# diban_v0_0.net
KiCad netlist of a schematic drawn in Altium Designer
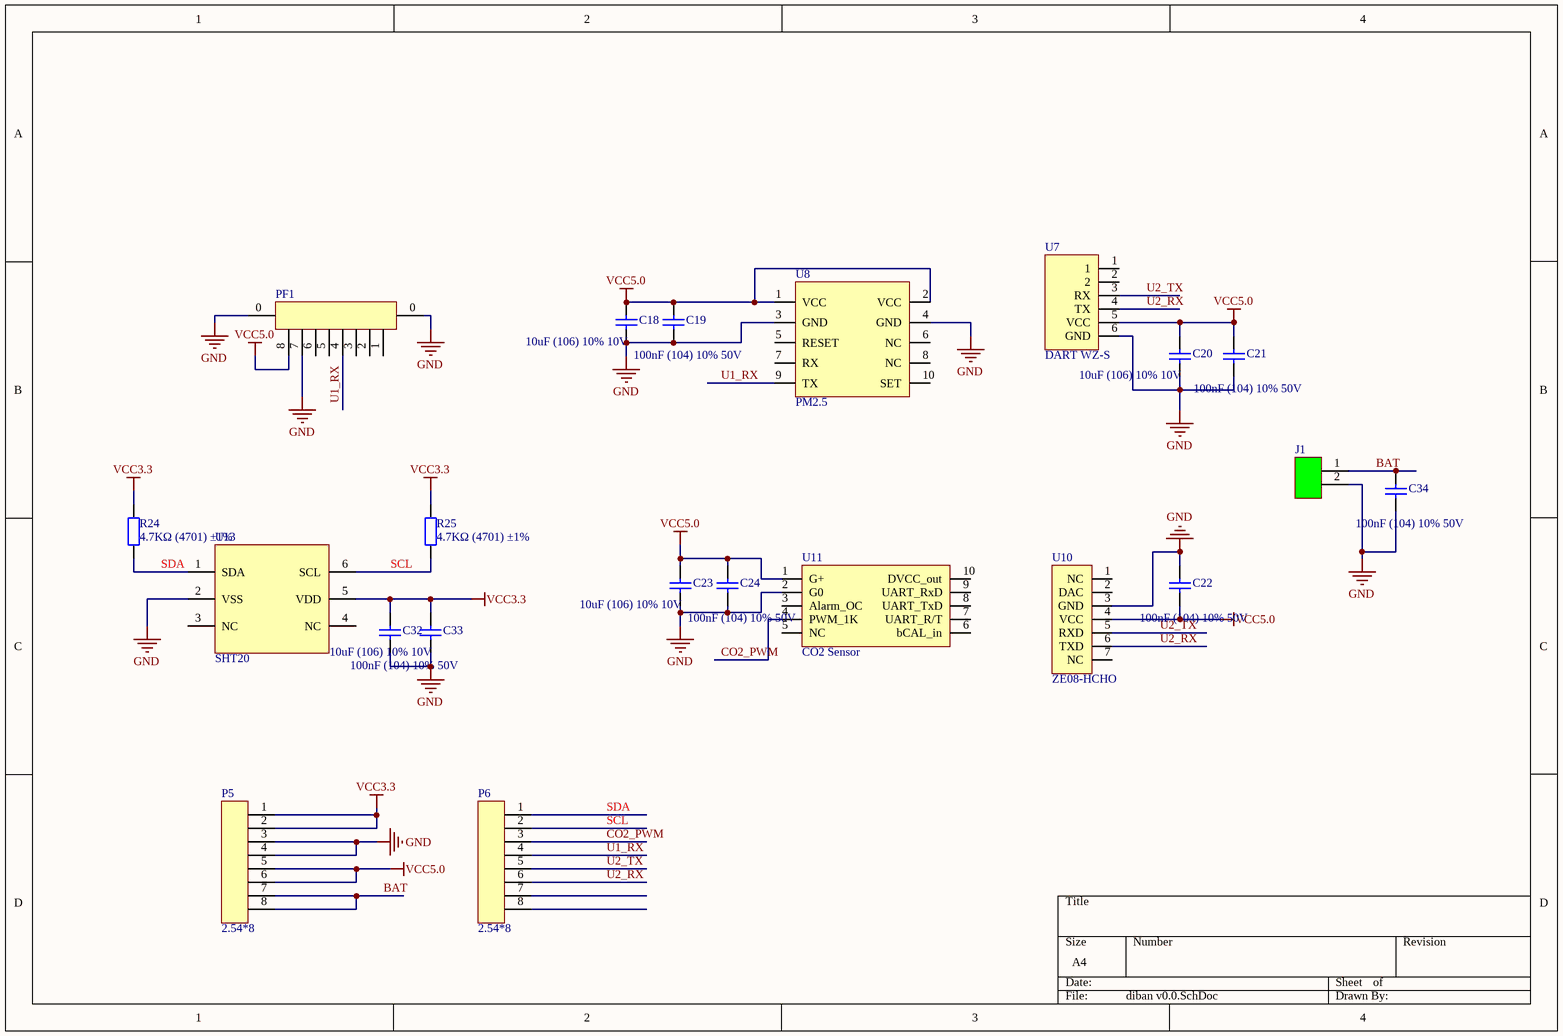
[diagram p0: diban v0.0.SchDoc]

(export (version "E")
  (design (tool "Eeschema 10.0.6"))
  (components
    (comp (ref "C18")
      (value "10uF (106) 10% 10V")
      (footprint "0603_C")
      (description "贴片电容")
      (libsource (lib "Miscellaneous Devices LC") (part "0603 10uF (106) 10% 10V"))
    )
    (comp (ref "C19")
      (value "100nF (104) 10% 50V")
      (footprint "0603_C")
      (description "贴片电容")
      (libsource (lib "Miscellaneous Devices LC") (part "0603 100nF (104) 10% 50V"))
    )
    (comp (ref "C20")
      (value "10uF (106) 10% 10V")
      (footprint "0603_C")
      (description "贴片电容")
      (libsource (lib "Miscellaneous Devices LC") (part "0603 10uF (106) 10% 10V"))
    )
    (comp (ref "C21")
      (value "100nF (104) 10% 50V")
      (footprint "0603_C")
      (description "贴片电容")
      (libsource (lib "Miscellaneous Devices LC") (part "0603 100nF (104) 10% 50V"))
    )
    (comp (ref "C22")
      (value "100nF (104) 10% 50V")
      (footprint "0603_C")
      (description "贴片电容")
      (libsource (lib "Miscellaneous Devices LC") (part "0603 100nF (104) 10% 50V"))
    )
    (comp (ref "C23")
      (value "10uF (106) 10% 10V")
      (footprint "0603_C")
      (description "贴片电容")
      (libsource (lib "Miscellaneous Devices LC") (part "0603 10uF (106) 10% 10V"))
    )
    (comp (ref "C24")
      (value "100nF (104) 10% 50V")
      (footprint "0603_C")
      (description "贴片电容")
      (libsource (lib "Miscellaneous Devices LC") (part "0603 100nF (104) 10% 50V"))
    )
    (comp (ref "C32")
      (value "100nF (104) 10% 50V")
      (footprint "0603_C")
      (description "贴片电容")
      (libsource (lib "Miscellaneous Devices LC") (part "0603 100nF (104) 10% 50V"))
    )
    (comp (ref "C33")
      (value "10uF (106) 10% 10V")
      (footprint "0603_C")
      (description "贴片电容")
      (libsource (lib "Miscellaneous Devices LC") (part "0603 10uF (106) 10% 10V"))
    )
    (comp (ref "C34")
      (value "100nF (104) 10% 50V")
      (footprint "0603_C")
      (description "贴片电容")
      (libsource (lib "Miscellaneous Devices LC") (part "0603 100nF (104) 10% 50V"))
    )
    (comp (ref "J1") (value "3.5mm-2p") (footprint "3.5mm-2p") (libsource (lib "接插件") (part "3.5mm-2p")))
    (comp (ref "P5") (value "2.54*8") (footprint "2.54*8") (libsource (lib "接插件") (part "2.54*8")))
    (comp (ref "P6") (value "2.54*8") (footprint "2.54*8") (libsource (lib "接插件") (part "2.54*8")))
    (comp (ref "PF1") (value "PCF-8") (footprint "PCF-8") (libsource (lib "接插件") (part "PCF-8")))
    (comp (ref "R24")
      (value "4.7KΩ (4701) ±1%")
      (footprint "0603_R")
      (description "贴片电阻")
      (libsource (lib "Miscellaneous Devices LC") (part "0603 4.7KΩ (4701) 1%"))
    )
    (comp (ref "R25")
      (value "4.7KΩ (4701) ±1%")
      (footprint "0603_R")
      (description "贴片电阻")
      (libsource (lib "Miscellaneous Devices LC") (part "0603 4.7KΩ (4701) 1%"))
    )
    (comp (ref "U7") (value "DART WZ-S") (footprint "DART WZ-S") (libsource (lib "集成块") (part "DART WZ-S")))
    (comp (ref "U8") (value "PM2.5") (footprint "PM2.5") (libsource (lib "集成块") (part "PM2.5")))
    (comp (ref "U10") (value "ZE08-HCHO") (footprint "ZE08-HCHO") (libsource (lib "集成块") (part "ZE08-HCHO")))
    (comp (ref "U11")
      (value "CO2 Sensor")
      (footprint "CO2 Sensor")
      (libsource (lib "集成块") (part "CO2 Sensor"))
    )
    (comp (ref "U13") (value "SHT20") (footprint "SHT20") (libsource (lib "集成块") (part "SHT20")))
  )
  (nets
    (net (code "1") (name "/BAT") (class "Default")
      (node (ref "C34") (pin "2") (pinfunction "2_2") (pintype "passive"))
      (node (ref "J1") (pin "1") (pintype "passive"))
      (node (ref "P5") (pin "7") (pintype "passive"))
      (node (ref "P5") (pin "8") (pinfunction "8_8") (pintype "passive"))
    )
    (net (code "2") (name "/CO2_PWM") (class "Default")
      (node (ref "P6") (pin "3") (pintype "passive"))
      (node (ref "U11") (pin "4") (pinfunction "PWM_1K_4") (pintype "passive"))
    )
    (net (code "3") (name "/SCL") (class "Default")
      (node (ref "P6") (pin "2") (pintype "passive"))
      (node (ref "R25") (pin "1") (pinfunction "1_1") (pintype "passive"))
      (node (ref "U13") (pin "6") (pinfunction "SCL_6") (pintype "passive"))
    )
    (net (code "4") (name "/SDA") (class "Default")
      (node (ref "P6") (pin "1") (pintype "passive"))
      (node (ref "R24") (pin "1") (pinfunction "1_1") (pintype "passive"))
      (node (ref "U13") (pin "1") (pinfunction "SDA_1") (pintype "passive"))
    )
    (net (code "5") (name "/U1_RX") (class "Default")
      (node (ref "P6") (pin "4") (pintype "passive"))
      (node (ref "PF1") (pin "4") (pintype "passive"))
      (node (ref "U8") (pin "9") (pinfunction "TX_9") (pintype "passive"))
    )
    (net (code "6") (name "/U2_RX") (class "Default")
      (node (ref "P6") (pin "6") (pintype "passive"))
      (node (ref "U10") (pin "6") (pinfunction "TXD_6") (pintype "passive"))
      (node (ref "U7") (pin "4") (pinfunction "TX_4") (pintype "passive"))
    )
    (net (code "7") (name "/U2_TX") (class "Default")
      (node (ref "P6") (pin "5") (pintype "passive"))
      (node (ref "U10") (pin "5") (pinfunction "RXD_5") (pintype "passive"))
      (node (ref "U7") (pin "3") (pinfunction "RX_3") (pintype "passive"))
    )
    (net (code "8") (name "GND") (class "Default")
      (node (ref "C18") (pin "1") (pinfunction "1_1") (pintype "passive"))
      (node (ref "C19") (pin "1") (pinfunction "1_1") (pintype "passive"))
      (node (ref "C20") (pin "1") (pinfunction "1_1") (pintype "passive"))
      (node (ref "C21") (pin "1") (pinfunction "1_1") (pintype "passive"))
      (node (ref "C22") (pin "2") (pinfunction "2_2") (pintype "passive"))
      (node (ref "C23") (pin "1") (pinfunction "1_1") (pintype "passive"))
      (node (ref "C24") (pin "1") (pinfunction "1_1") (pintype "passive"))
      (node (ref "C32") (pin "1") (pinfunction "1_1") (pintype "passive"))
      (node (ref "C33") (pin "1") (pinfunction "1_1") (pintype "passive"))
      (node (ref "C34") (pin "1") (pinfunction "1_1") (pintype "passive"))
      (node (ref "J1") (pin "2") (pintype "passive"))
      (node (ref "P5") (pin "3") (pintype "passive"))
      (node (ref "P5") (pin "4") (pintype "passive"))
      (node (ref "PF1") (pin "0") (pintype "passive"))
      (node (ref "PF1") (pin "7") (pintype "passive"))
      (node (ref "U10") (pin "3") (pinfunction "GND_3") (pintype "passive"))
      (node (ref "U11") (pin "2") (pinfunction "G0_2") (pintype "passive"))
      (node (ref "U13") (pin "2") (pinfunction "VSS_2") (pintype "passive"))
      (node (ref "U7") (pin "6") (pinfunction "GND_6") (pintype "passive"))
      (node (ref "U8") (pin "3") (pinfunction "GND_3") (pintype "passive"))
      (node (ref "U8") (pin "4") (pinfunction "GND_4") (pintype "passive"))
    )
    (net (code "9") (name "VCC3.3") (class "Default")
      (node (ref "C32") (pin "2") (pinfunction "2_2") (pintype "passive"))
      (node (ref "C33") (pin "2") (pinfunction "2_2") (pintype "passive"))
      (node (ref "P5") (pin "1") (pintype "passive"))
      (node (ref "P5") (pin "2") (pintype "passive"))
      (node (ref "R24") (pin "2") (pinfunction "2_2") (pintype "passive"))
      (node (ref "R25") (pin "2") (pinfunction "2_2") (pintype "passive"))
      (node (ref "U13") (pin "5") (pinfunction "VDD_5") (pintype "passive"))
    )
    (net (code "10") (name "VCC5.0") (class "Default")
      (node (ref "C18") (pin "2") (pinfunction "2_2") (pintype "passive"))
      (node (ref "C19") (pin "2") (pinfunction "2_2") (pintype "passive"))
      (node (ref "C20") (pin "2") (pinfunction "2_2") (pintype "passive"))
      (node (ref "C21") (pin "2") (pinfunction "2_2") (pintype "passive"))
      (node (ref "C22") (pin "1") (pinfunction "1_1") (pintype "passive"))
      (node (ref "C23") (pin "2") (pinfunction "2_2") (pintype "passive"))
      (node (ref "C24") (pin "2") (pinfunction "2_2") (pintype "passive"))
      (node (ref "P5") (pin "5") (pintype "passive"))
      (node (ref "P5") (pin "6") (pintype "passive"))
      (node (ref "PF1") (pin "8") (pinfunction "8_8") (pintype "passive"))
      (node (ref "U10") (pin "4") (pinfunction "VCC_4") (pintype "passive"))
      (node (ref "U11") (pin "1") (pinfunction "G+_1") (pintype "passive"))
      (node (ref "U7") (pin "5") (pinfunction "VCC_5") (pintype "passive"))
      (node (ref "U8") (pin "1") (pinfunction "VCC_1") (pintype "passive"))
      (node (ref "U8") (pin "2") (pinfunction "VCC_2") (pintype "passive"))
    )
    (net (code "11") (name "unconnected-(P6-Pad7)") (class "Default")
      (node (ref "P6") (pin "7") (pintype "passive"))
    )
    (net (code "12") (name "unconnected-(P6-Pad8)") (class "Default")
      (node (ref "P6") (pin "8") (pinfunction "8_8") (pintype "passive"))
    )
    (net (code "13") (name "unconnected-(PF1-Pad1)") (class "Default")
      (node (ref "PF1") (pin "1") (pintype "passive"))
    )
    (net (code "14") (name "unconnected-(PF1-Pad2)") (class "Default")
      (node (ref "PF1") (pin "2") (pintype "passive"))
    )
    (net (code "15") (name "unconnected-(PF1-Pad3)") (class "Default")
      (node (ref "PF1") (pin "3") (pintype "passive"))
    )
    (net (code "16") (name "unconnected-(PF1-Pad5)") (class "Default")
      (node (ref "PF1") (pin "5") (pintype "passive"))
    )
    (net (code "17") (name "unconnected-(PF1-Pad6)") (class "Default")
      (node (ref "PF1") (pin "6") (pintype "passive"))
    )
    (net (code "18") (name "unconnected-(U7-Pad1)") (class "Default")
      (node (ref "U7") (pin "1") (pinfunction "1_1") (pintype "passive"))
    )
    (net (code "19") (name "unconnected-(U7-Pad2)") (class "Default")
      (node (ref "U7") (pin "2") (pinfunction "2_2") (pintype "passive"))
    )
    (net (code "20") (name "unconnected-(U8-NC-Pad6)") (class "Default")
      (node (ref "U8") (pin "6") (pinfunction "NC_6") (pintype "passive"))
    )
    (net (code "21") (name "unconnected-(U8-NC-Pad8)") (class "Default")
      (node (ref "U8") (pin "8") (pinfunction "NC_8") (pintype "passive"))
    )
    (net (code "22") (name "unconnected-(U8-RESET-Pad5)") (class "Default")
      (node (ref "U8") (pin "5") (pinfunction "RESET_5") (pintype "passive"))
    )
    (net (code "23") (name "unconnected-(U8-RX-Pad7)") (class "Default")
      (node (ref "U8") (pin "7") (pinfunction "RX_7") (pintype "passive"))
    )
    (net (code "24") (name "unconnected-(U8-SET-Pad10)") (class "Default")
      (node (ref "U8") (pin "10") (pinfunction "SET_10") (pintype "passive"))
    )
    (net (code "25") (name "unconnected-(U10-DAC-Pad2)") (class "Default")
      (node (ref "U10") (pin "2") (pinfunction "DAC_2") (pintype "passive"))
    )
    (net (code "26") (name "unconnected-(U10-NC-Pad1)") (class "Default")
      (node (ref "U10") (pin "1") (pinfunction "NC_1") (pintype "passive"))
    )
    (net (code "27") (name "unconnected-(U10-NC-Pad7)") (class "Default")
      (node (ref "U10") (pin "7") (pinfunction "NC_7") (pintype "passive"))
    )
    (net (code "28") (name "unconnected-(U11-Alarm_OC-Pad3)") (class "Default")
      (node (ref "U11") (pin "3") (pinfunction "Alarm_OC_3") (pintype "passive"))
    )
    (net (code "29") (name "unconnected-(U11-DVCC_out-Pad10)") (class "Default")
      (node (ref "U11") (pin "10") (pinfunction "DVCC_out_10") (pintype "passive"))
    )
    (net (code "30") (name "unconnected-(U11-NC-Pad5)") (class "Default")
      (node (ref "U11") (pin "5") (pinfunction "NC_5") (pintype "passive"))
    )
    (net (code "31") (name "unconnected-(U11-UART_RxD-Pad9)") (class "Default")
      (node (ref "U11") (pin "9") (pinfunction "UART_RxD_9") (pintype "passive"))
    )
    (net (code "32") (name "unconnected-(U11-UART_R{slash}T-Pad7)") (class "Default")
      (node (ref "U11") (pin "7") (pinfunction "UART_R/T_7") (pintype "passive"))
    )
    (net (code "33") (name "unconnected-(U11-UART_TxD-Pad8)") (class "Default")
      (node (ref "U11") (pin "8") (pinfunction "UART_TxD_8") (pintype "passive"))
    )
    (net (code "34") (name "unconnected-(U11-bCAL_in-Pad6)") (class "Default")
      (node (ref "U11") (pin "6") (pinfunction "bCAL_in_6") (pintype "passive"))
    )
    (net (code "35") (name "unconnected-(U13-NC-Pad3)") (class "Default")
      (node (ref "U13") (pin "3") (pinfunction "NC_3") (pintype "passive"))
    )
    (net (code "36") (name "unconnected-(U13-NC-Pad4)") (class "Default")
      (node (ref "U13") (pin "4") (pinfunction "NC_4") (pintype "passive"))
    )
  )
)
